# Sheet1.net
KiCad netlist of a schematic drawn in Altium Designer
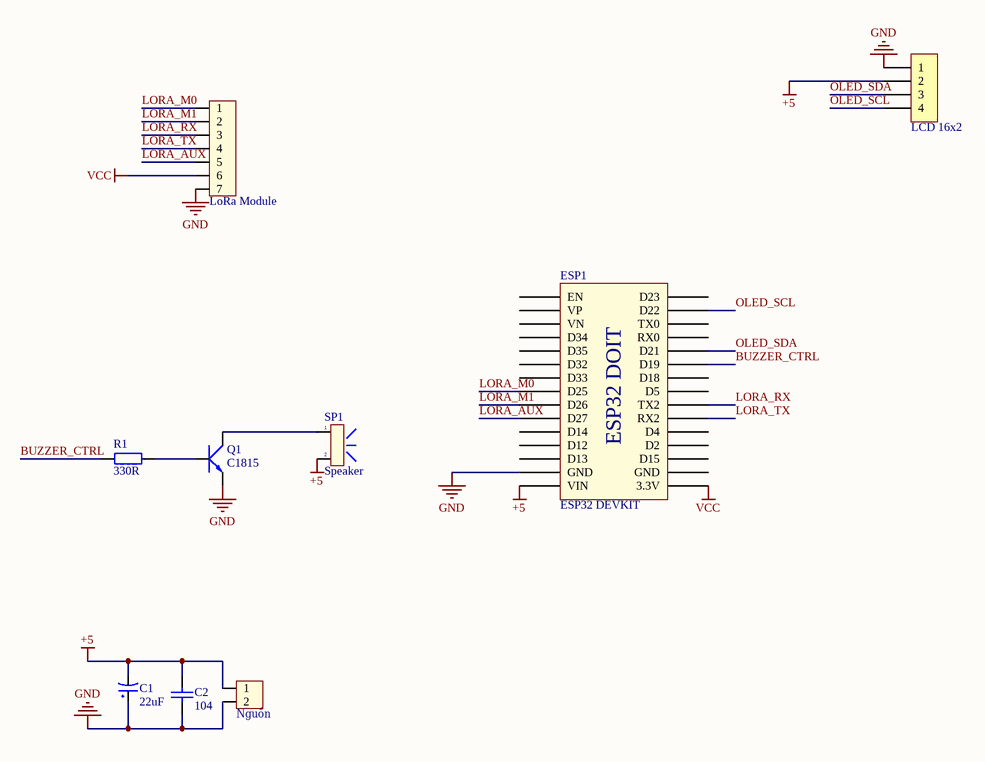
[diagram p0: Sheet1.SchDoc]

(export (version "E")
  (design (tool "Eeschema 10.0.6"))
  (components
    (comp (ref "C1")
      (value "22uF")
      (footprint "tu hoa 4mm")
      (description "Cắm")
      (libsource (lib "AltiumLib_KhueNguyenCreator") (part "Tu Hoa 22uF 16V 4x7"))
    )
    (comp (ref "C2")
      (value "104")
      (footprint "tu gom")
      (description "Cắm")
      (libsource (lib "AltiumLib_KhueNguyenCreator") (part "Tu gom 104 50V"))
    )
    (comp (ref "ESP1")
      (value "ESP32 DEVKIT")
      (footprint "ESP32 WROOM 32 KIT")
      (libsource (lib "AltiumLib_KhueNguyenCreator") (part "ESP32 WROOM 32 KIT"))
    )
    (comp (ref "H1")
      (value "LCD 16x2")
      (footprint "Header 4P DC 2.54")
      (description "Cắm")
      (libsource (lib "AltiumLib_KhueNguyenCreator") (part "Header 4P 2.54 Duc Cong"))
    )
    (comp (ref "H2")
      (value "LoRa Module")
      (footprint "Header 7P DC 2.54")
      (description "Cắm")
      (libsource (lib "AltiumLib_KhueNguyenCreator") (part "Header 7P 2.54 Duc Cong"))
    )
    (comp (ref "H3")
      (value "Nguồn")
      (footprint "Header 2P DC 2.54")
      (description "Cắm")
      (libsource (lib "AltiumLib_KhueNguyenCreator") (part "Header 2P 2.54 Duc Cong"))
    )
    (comp (ref "Q1")
      (value "C1815")
      (footprint "TO92")
      (description "NPN transistor")
      (libsource (lib "AltiumLib_KhueNguyenCreator") (part "Trans C1815 DIP"))
    )
    (comp (ref "R1")
      (value "330R")
      (footprint "tro vach 1/4w")
      (description "Cắm")
      (libsource (lib "AltiumLib_KhueNguyenCreator") (part "Tro Vach 1/4W 1% 330R"))
    )
    (comp (ref "SP1")
      (value "Speaker")
      (footprint "SPK")
      (description "Speaker Chip")
      (libsource (lib "4.Thuvien3D") (part "SPK"))
    )
  )
  (nets
    (net (code "1") (name "+5") (class "Default")
      (node (ref "C1") (pin "2") (pinfunction "2_2") (pintype "passive"))
      (node (ref "C2") (pin "1") (pinfunction "1_1") (pintype "passive"))
      (node (ref "ESP1") (pin "15") (pinfunction "VIN_15") (pintype "passive"))
      (node (ref "H1") (pin "2") (pinfunction "2_2") (pintype "passive"))
      (node (ref "H3") (pin "1") (pinfunction "1_1") (pintype "passive"))
      (node (ref "SP1") (pin "2") (pinfunction "2_2") (pintype "passive"))
    )
    (net (code "2") (name "/BUZZER_CTRL") (class "Default")
      (node (ref "ESP1") (pin "25") (pinfunction "D19_25") (pintype "passive"))
      (node (ref "R1") (pin "1") (pinfunction "1_1") (pintype "passive"))
    )
    (net (code "3") (name "/LORA_AUX") (class "Default")
      (node (ref "ESP1") (pin "10") (pinfunction "D27_10") (pintype "passive"))
      (node (ref "H2") (pin "5") (pinfunction "5_5") (pintype "passive"))
    )
    (net (code "4") (name "/LORA_M0") (class "Default")
      (node (ref "ESP1") (pin "8") (pinfunction "D25_8") (pintype "passive"))
      (node (ref "H2") (pin "1") (pinfunction "1_1") (pintype "passive"))
    )
    (net (code "5") (name "/LORA_M1") (class "Default")
      (node (ref "ESP1") (pin "9") (pinfunction "D26_9") (pintype "passive"))
      (node (ref "H2") (pin "2") (pinfunction "2_2") (pintype "passive"))
    )
    (net (code "6") (name "/LORA_RX") (class "Default")
      (node (ref "ESP1") (pin "22") (pinfunction "TX2_22") (pintype "passive"))
      (node (ref "H2") (pin "3") (pinfunction "3_3") (pintype "passive"))
    )
    (net (code "7") (name "/LORA_TX") (class "Default")
      (node (ref "ESP1") (pin "21") (pinfunction "RX2_21") (pintype "passive"))
      (node (ref "H2") (pin "4") (pinfunction "4_4") (pintype "passive"))
    )
    (net (code "8") (name "/OLED_SCL") (class "Default")
      (node (ref "ESP1") (pin "29") (pinfunction "D22_29") (pintype "passive"))
      (node (ref "H1") (pin "4") (pinfunction "4_4") (pintype "passive"))
    )
    (net (code "9") (name "/OLED_SDA") (class "Default")
      (node (ref "ESP1") (pin "26") (pinfunction "D21_26") (pintype "passive"))
      (node (ref "H1") (pin "3") (pinfunction "3_3") (pintype "passive"))
    )
    (net (code "10") (name "GND") (class "Default")
      (node (ref "C1") (pin "1") (pinfunction "1_1") (pintype "passive"))
      (node (ref "C2") (pin "2") (pinfunction "2_2") (pintype "passive"))
      (node (ref "ESP1") (pin "14") (pinfunction "GND_14") (pintype "passive"))
      (node (ref "H1") (pin "1") (pinfunction "1_1") (pintype "passive"))
      (node (ref "H2") (pin "7") (pinfunction "7_7") (pintype "passive"))
      (node (ref "H3") (pin "2") (pinfunction "2_2") (pintype "passive"))
      (node (ref "Q1") (pin "1") (pinfunction "E_1") (pintype "passive"))
    )
    (net (code "11") (name "Net-(Q1-B)") (class "Default")
      (node (ref "Q1") (pin "3") (pinfunction "B_3") (pintype "passive"))
      (node (ref "R1") (pin "2") (pinfunction "2_2") (pintype "passive"))
    )
    (net (code "12") (name "Net-(Q1-C)") (class "Default")
      (node (ref "Q1") (pin "2") (pinfunction "C_2") (pintype "passive"))
      (node (ref "SP1") (pin "1") (pinfunction "1_1") (pintype "passive"))
    )
    (net (code "13") (name "VCC") (class "Default")
      (node (ref "ESP1") (pin "16") (pinfunction "3.3V_16") (pintype "passive"))
      (node (ref "H2") (pin "6") (pinfunction "6_6") (pintype "passive"))
    )
    (net (code "14") (name "unconnected-(ESP1-D2-Pad19)") (class "Default")
      (node (ref "ESP1") (pin "19") (pinfunction "D2_19") (pintype "passive"))
    )
    (net (code "15") (name "unconnected-(ESP1-D4-Pad20)") (class "Default")
      (node (ref "ESP1") (pin "20") (pinfunction "D4_20") (pintype "passive"))
    )
    (net (code "16") (name "unconnected-(ESP1-D5-Pad23)") (class "Default")
      (node (ref "ESP1") (pin "23") (pinfunction "D5_23") (pintype "passive"))
    )
    (net (code "17") (name "unconnected-(ESP1-D12-Pad12)") (class "Default")
      (node (ref "ESP1") (pin "12") (pinfunction "D12_12") (pintype "passive"))
    )
    (net (code "18") (name "unconnected-(ESP1-D13-Pad13)") (class "Default")
      (node (ref "ESP1") (pin "13") (pinfunction "D13_13") (pintype "passive"))
    )
    (net (code "19") (name "unconnected-(ESP1-D14-Pad11)") (class "Default")
      (node (ref "ESP1") (pin "11") (pinfunction "D14_11") (pintype "passive"))
    )
    (net (code "20") (name "unconnected-(ESP1-D15-Pad18)") (class "Default")
      (node (ref "ESP1") (pin "18") (pinfunction "D15_18") (pintype "passive"))
    )
    (net (code "21") (name "unconnected-(ESP1-D18-Pad24)") (class "Default")
      (node (ref "ESP1") (pin "24") (pinfunction "D18_24") (pintype "passive"))
    )
    (net (code "22") (name "unconnected-(ESP1-D23-Pad30)") (class "Default")
      (node (ref "ESP1") (pin "30") (pinfunction "D23_30") (pintype "passive"))
    )
    (net (code "23") (name "unconnected-(ESP1-D32-Pad6)") (class "Default")
      (node (ref "ESP1") (pin "6") (pinfunction "D32_6") (pintype "passive"))
    )
    (net (code "24") (name "unconnected-(ESP1-D33-Pad7)") (class "Default")
      (node (ref "ESP1") (pin "7") (pinfunction "D33_7") (pintype "passive"))
    )
    (net (code "25") (name "unconnected-(ESP1-D34-Pad4)") (class "Default")
      (node (ref "ESP1") (pin "4") (pinfunction "D34_4") (pintype "passive"))
    )
    (net (code "26") (name "unconnected-(ESP1-D35-Pad5)") (class "Default")
      (node (ref "ESP1") (pin "5") (pinfunction "D35_5") (pintype "passive"))
    )
    (net (code "27") (name "unconnected-(ESP1-EN-Pad1)") (class "Default")
      (node (ref "ESP1") (pin "1") (pinfunction "EN_1") (pintype "passive"))
    )
    (net (code "28") (name "unconnected-(ESP1-GND-Pad17)") (class "Default")
      (node (ref "ESP1") (pin "17") (pinfunction "GND_17") (pintype "passive"))
    )
    (net (code "29") (name "unconnected-(ESP1-RX0-Pad27)") (class "Default")
      (node (ref "ESP1") (pin "27") (pinfunction "RX0_27") (pintype "passive"))
    )
    (net (code "30") (name "unconnected-(ESP1-TX0-Pad28)") (class "Default")
      (node (ref "ESP1") (pin "28") (pinfunction "TX0_28") (pintype "passive"))
    )
    (net (code "31") (name "unconnected-(ESP1-VN-Pad3)") (class "Default")
      (node (ref "ESP1") (pin "3") (pinfunction "VN_3") (pintype "passive"))
    )
    (net (code "32") (name "unconnected-(ESP1-VP-Pad2)") (class "Default")
      (node (ref "ESP1") (pin "2") (pinfunction "VP_2") (pintype "passive"))
    )
  )
)
